# Lichtplatine.net
KiCad netlist of a schematic drawn in EAGLE
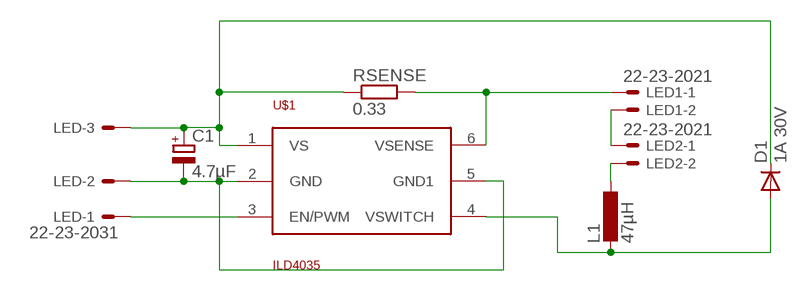
[diagram p0: schematic, sheet 1]

(export (version "E")
  (design (tool "Eeschema 10.0.6"))
  (components
    (comp (ref "C1")
      (value "4.7µF")
      (footprint "eagle-import:E2,5-5")
      (libsource (lib "eagle-import") (part "CPOL-EUE2.5-5"))
    )
    (comp (ref "D1")
      (value "1A 30V")
      (footprint "eagle-import:DO41-7.6")
      (libsource (lib "eagle-import") (part "DIODE-DO41-7.6"))
    )
    (comp (ref "L1")
      (value "47µH")
      (footprint "eagle-import:6000-XXXX-RC")
      (libsource (lib "eagle-import") (part "L-EU6000-XXX-RC"))
    )
    (comp (ref "LED")
      (value "22-23-2031")
      (footprint "eagle-import:22-23-2031")
      (fields (field (name "MF") "MOLEX"))
      (libsource (lib "eagle-import") (part "22-23-2031"))
    )
    (comp (ref "LED1")
      (value "22-23-2021")
      (footprint "eagle-import:22-23-2021")
      (fields (field (name "MF") "MOLEX"))
      (libsource (lib "eagle-import") (part "22-23-2021"))
    )
    (comp (ref "LED2")
      (value "22-23-2021")
      (footprint "eagle-import:22-23-2021")
      (fields (field (name "MF") "MOLEX"))
      (libsource (lib "eagle-import") (part "22-23-2021"))
    )
    (comp (ref "RSENSE")
      (value "0.33")
      (footprint "eagle-import:R2010")
      (libsource (lib "eagle-import") (part "R-EU_R2010"))
    )
    (comp (ref "U$1")
      (value "ILD4035")
      (footprint "eagle-import:SC74")
      (libsource (lib "eagle-import") (part "ILD4035"))
    )
  )
  (nets
    (net (code "1") (name "Net-(LED1A-S)") (class "Default")
      (node (ref "LED1") (pin "1") (pinfunction "S_1") (pintype "passive"))
      (node (ref "RSENSE") (pin "2") (pinfunction "2_2") (pintype "passive"))
      (node (ref "U$1") (pin "6") (pinfunction "VSENSE_6") (pintype "bidirectional"))
    )
    (net (code "2") (name "Net-(LED1B-S)") (class "Default")
      (node (ref "LED1") (pin "2") (pinfunction "S_2") (pintype "passive"))
      (node (ref "LED2") (pin "1") (pinfunction "S_1") (pintype "passive"))
    )
    (net (code "3") (name "Net-(LED2B-S)") (class "Default")
      (node (ref "L1") (pin "1") (pinfunction "1_1") (pintype "passive"))
      (node (ref "LED2") (pin "2") (pinfunction "S_2") (pintype "passive"))
    )
    (net (code "4") (name "Net-(LEDA-S)") (class "Default")
      (node (ref "LED") (pin "1") (pinfunction "S_1") (pintype "passive"))
      (node (ref "U$1") (pin "3") (pinfunction "EN/PWM_3") (pintype "bidirectional"))
    )
    (net (code "5") (name "Net-(LEDB-S)") (class "Default")
      (node (ref "C1") (pin "-") (pinfunction "-_-") (pintype "passive"))
      (node (ref "LED") (pin "2") (pinfunction "S_2") (pintype "passive"))
      (node (ref "U$1") (pin "2") (pinfunction "GND_2") (pintype "bidirectional"))
      (node (ref "U$1") (pin "5") (pinfunction "GND1_5") (pintype "bidirectional"))
    )
    (net (code "6") (name "Net-(LEDC-S)") (class "Default")
      (node (ref "C1") (pin "+") (pinfunction "+_+") (pintype "passive"))
      (node (ref "D1") (pin "C") (pinfunction "C_C") (pintype "passive"))
      (node (ref "LED") (pin "3") (pinfunction "S_3") (pintype "passive"))
      (node (ref "RSENSE") (pin "1") (pinfunction "1_1") (pintype "passive"))
      (node (ref "U$1") (pin "1") (pinfunction "VS_1") (pintype "bidirectional"))
    )
    (net (code "7") (name "Net-(U$1-VSWITCH)") (class "Default")
      (node (ref "D1") (pin "A") (pinfunction "A_A") (pintype "passive"))
      (node (ref "L1") (pin "2") (pinfunction "2_2") (pintype "passive"))
      (node (ref "U$1") (pin "4") (pinfunction "VSWITCH_4") (pintype "bidirectional"))
    )
  )
)
